# psu.net
KiCad netlist of a schematic drawn in Altium Designer
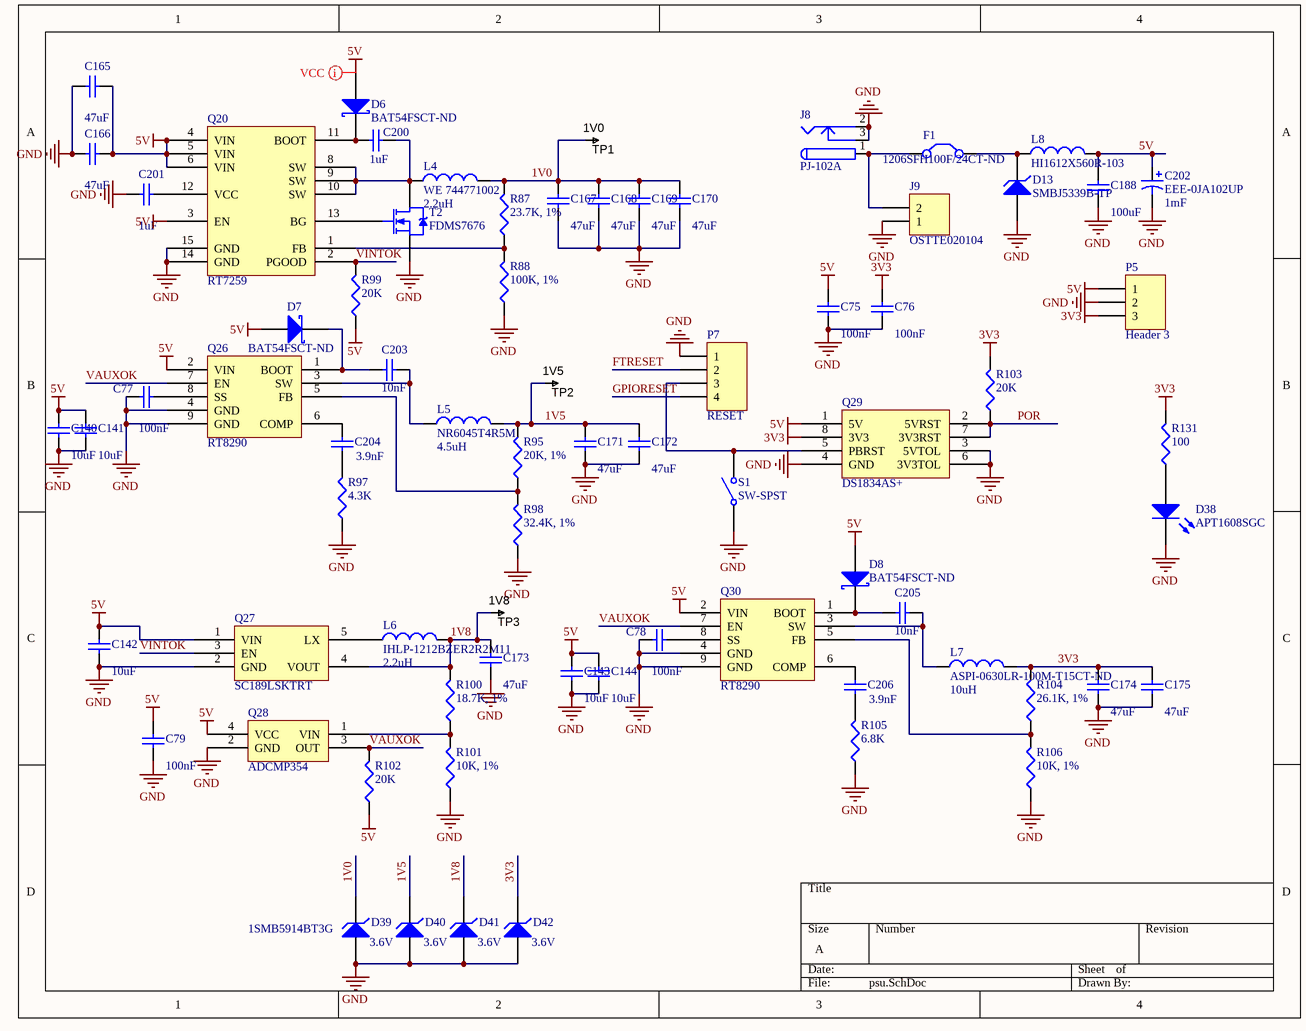
[diagram p0: psu.SchDoc]

(export (version "E")
  (design (tool "Eeschema 10.0.6"))
  (components
    (comp (ref "C75")
      (value "100nF")
      (footprint "CAPC1005X06L")
      (description "Capacitor")
      (fields (field (name "Comment") "Cap") (field (name "PUBLISHER") "Altium Limited"))
      (libsource (lib "Miscellaneous Devices") (part "Cap"))
    )
    (comp (ref "C76")
      (value "100nF")
      (footprint "CAPC1005X06L")
      (description "Capacitor")
      (fields (field (name "Comment") "Cap") (field (name "PUBLISHER") "Altium Limited"))
      (libsource (lib "Miscellaneous Devices") (part "Cap"))
    )
    (comp (ref "C77")
      (value "100nF")
      (footprint "CAPC1005X06L")
      (description "Capacitor")
      (fields (field (name "Comment") "Cap") (field (name "PUBLISHER") "Altium Limited"))
      (libsource (lib "Miscellaneous Devices") (part "Cap"))
    )
    (comp (ref "C78")
      (value "100nF")
      (footprint "CAPC1005X06L")
      (description "Capacitor")
      (fields (field (name "Comment") "Cap") (field (name "PUBLISHER") "Altium Limited"))
      (libsource (lib "Miscellaneous Devices") (part "Cap"))
    )
    (comp (ref "C79")
      (value "100nF")
      (footprint "CAPC1005X06L")
      (description "Capacitor")
      (fields (field (name "Comment") "Cap") (field (name "PUBLISHER") "Altium Limited"))
      (libsource (lib "Miscellaneous Devices") (part "Cap"))
    )
    (comp (ref "C140")
      (value "10uF")
      (footprint "CAPC1608X90N")
      (description "Capacitor")
      (fields (field (name "Comment") "GRM188R60G106ME47") (field (name "PUBLISHER") "Altium Limited"))
      (libsource (lib "Miscellaneous Devices") (part "Cap"))
    )
    (comp (ref "C141")
      (value "10uF")
      (footprint "CAPC1608X90N")
      (description "Capacitor")
      (fields (field (name "Comment") "GRM188R60G106ME47") (field (name "PUBLISHER") "Altium Limited"))
      (libsource (lib "Miscellaneous Devices") (part "Cap"))
    )
    (comp (ref "C142")
      (value "10uF")
      (footprint "CAPC1608X90N")
      (description "Capacitor")
      (fields (field (name "Comment") "GRM188R60G106ME47") (field (name "PUBLISHER") "Altium Limited"))
      (libsource (lib "Miscellaneous Devices") (part "Cap"))
    )
    (comp (ref "C143")
      (value "10uF")
      (footprint "CAPC1608X90N")
      (description "Capacitor")
      (fields (field (name "Comment") "GRM188R60G106ME47") (field (name "PUBLISHER") "Altium Limited"))
      (libsource (lib "Miscellaneous Devices") (part "Cap"))
    )
    (comp (ref "C144")
      (value "10uF")
      (footprint "CAPC1608X90N")
      (description "Capacitor")
      (fields (field (name "Comment") "GRM188R60G106ME47") (field (name "PUBLISHER") "Altium Limited"))
      (libsource (lib "Miscellaneous Devices") (part "Cap"))
    )
    (comp (ref "C165")
      (value "47uF")
      (footprint "CAPC3225X220N")
      (description "Capacitor")
      (fields (field (name "Comment") "GRM31CR60J476ME19L") (field (name "PUBLISHER") "Altium Limited"))
      (libsource (lib "Miscellaneous Devices") (part "Cap"))
    )
    (comp (ref "C166")
      (value "47uF")
      (footprint "CAPC3225X220N")
      (description "Capacitor")
      (fields (field (name "Comment") "GRM31CR60J476ME19L") (field (name "PUBLISHER") "Altium Limited"))
      (libsource (lib "Miscellaneous Devices") (part "Cap"))
    )
    (comp (ref "C167")
      (value "47uF")
      (footprint "CAPC3225X220N")
      (description "Capacitor")
      (fields (field (name "Comment") "GRM31CR60J476ME19L") (field (name "PUBLISHER") "Altium Limited"))
      (libsource (lib "Miscellaneous Devices") (part "Cap"))
    )
    (comp (ref "C168")
      (value "47uF")
      (footprint "CAPC3225X220N")
      (description "Capacitor")
      (fields (field (name "Comment") "GRM31CR60J476ME19L") (field (name "PUBLISHER") "Altium Limited"))
      (libsource (lib "Miscellaneous Devices") (part "Cap"))
    )
    (comp (ref "C169")
      (value "47uF")
      (footprint "CAPC3225X220N")
      (description "Capacitor")
      (fields (field (name "Comment") "GRM31CR60J476ME19L") (field (name "PUBLISHER") "Altium Limited"))
      (libsource (lib "Miscellaneous Devices") (part "Cap"))
    )
    (comp (ref "C170")
      (value "47uF")
      (footprint "CAPC3225X220N")
      (description "Capacitor")
      (fields (field (name "Comment") "GRM31CR60J476ME19L") (field (name "PUBLISHER") "Altium Limited"))
      (libsource (lib "Miscellaneous Devices") (part "Cap"))
    )
    (comp (ref "C171")
      (value "47uF")
      (footprint "CAPC3225X220N")
      (description "Capacitor")
      (fields (field (name "Comment") "GRM31CR60J476ME19L") (field (name "PUBLISHER") "Altium Limited"))
      (libsource (lib "Miscellaneous Devices") (part "Cap"))
    )
    (comp (ref "C172")
      (value "47uF")
      (footprint "CAPC3225X220N")
      (description "Capacitor")
      (fields (field (name "Comment") "GRM31CR60J476ME19L") (field (name "PUBLISHER") "Altium Limited"))
      (libsource (lib "Miscellaneous Devices") (part "Cap"))
    )
    (comp (ref "C173")
      (value "47uF")
      (footprint "CAPC3225X220N")
      (description "Capacitor")
      (fields (field (name "Comment") "GRM31CR60J476ME19L") (field (name "PUBLISHER") "Altium Limited"))
      (libsource (lib "Miscellaneous Devices") (part "Cap"))
    )
    (comp (ref "C174")
      (value "47uF")
      (footprint "CAPC3225X220N")
      (description "Capacitor")
      (fields (field (name "Comment") "GRM31CR60J476ME19L") (field (name "PUBLISHER") "Altium Limited"))
      (libsource (lib "Miscellaneous Devices") (part "Cap"))
    )
    (comp (ref "C175")
      (value "47uF")
      (footprint "CAPC3225X220N")
      (description "Capacitor")
      (fields (field (name "Comment") "GRM31CR60J476ME19L") (field (name "PUBLISHER") "Altium Limited"))
      (libsource (lib "Miscellaneous Devices") (part "Cap"))
    )
    (comp (ref "C188")
      (value "100uF")
      (footprint "CAPC3225X220N")
      (description "Capacitor")
      (fields (field (name "Comment") "GRM31CR60J107ME39L") (field (name "PUBLISHER") "Altium Limited"))
      (libsource (lib "Miscellaneous Devices") (part "Cap"))
    )
    (comp (ref "C200")
      (value "1uF")
      (footprint "CAPC1608X90N")
      (description "Capacitor")
      (fields (field (name "Comment") "GRM188R60J105KA01D") (field (name "PUBLISHER") "Altium Limited"))
      (libsource (lib "Miscellaneous Devices") (part "Cap"))
    )
    (comp (ref "C201")
      (value "1uF")
      (footprint "CAPC1608X90N")
      (description "Capacitor")
      (fields (field (name "Comment") "GRM188R60J105KA01D") (field (name "PUBLISHER") "Altium Limited"))
      (libsource (lib "Miscellaneous Devices") (part "Cap"))
    )
    (comp (ref "C202")
      (value "EEE-0JA102UP")
      (footprint "CAP_ELEC_SIZE_E")
      (description "Polarized Capacitor (Radial)")
      (fields (field (name "ALTIUM_VALUE") "1mF") (field (name "PUBLISHER") "Altium Limited"))
      (libsource (lib "Miscellaneous Devices") (part "Cap Pol1"))
    )
    (comp (ref "C203")
      (value "10nF")
      (footprint "CAPC1005X06L")
      (description "Capacitor")
      (fields (field (name "Comment") "GRM188R71H103KA01D") (field (name "PUBLISHER") "Altium Limited"))
      (libsource (lib "Miscellaneous Devices") (part "Cap"))
    )
    (comp (ref "C204")
      (value "3.9nF")
      (footprint "CAPC1608X90N")
      (description "Capacitor")
      (fields (field (name "Comment") "CL10B393KO8NNNC") (field (name "PUBLISHER") "Altium Limited"))
      (libsource (lib "Miscellaneous Devices") (part "Cap"))
    )
    (comp (ref "C205")
      (value "10nF")
      (footprint "CAPC1005X06L")
      (description "Capacitor")
      (fields (field (name "Comment") "GRM188R71H103KA01D") (field (name "PUBLISHER") "Altium Limited"))
      (libsource (lib "Miscellaneous Devices") (part "Cap"))
    )
    (comp (ref "C206")
      (value "3.9nF")
      (footprint "CAPC1608X90N")
      (description "Capacitor")
      (fields (field (name "Comment") "CL10B393KO8NNNC") (field (name "PUBLISHER") "Altium Limited"))
      (libsource (lib "Miscellaneous Devices") (part "Cap"))
    )
    (comp (ref "D6")
      (value "BAT54FSCT-ND")
      (footprint "BAT54")
      (description "Schottky Diode")
      (fields (field (name "PUBLISHER") "Altium Limited"))
      (libsource (lib "Miscellaneous Devices") (part "D Schottky"))
    )
    (comp (ref "D7")
      (value "BAT54FSCT-ND")
      (footprint "BAT54")
      (description "Schottky Diode")
      (fields (field (name "PUBLISHER") "Altium Limited"))
      (libsource (lib "Miscellaneous Devices") (part "D Schottky"))
    )
    (comp (ref "D8")
      (value "BAT54FSCT-ND")
      (footprint "BAT54")
      (description "Schottky Diode")
      (fields (field (name "PUBLISHER") "Altium Limited"))
      (libsource (lib "Miscellaneous Devices") (part "D Schottky"))
    )
    (comp (ref "D13")
      (value "SMBJ5339B-TP")
      (footprint "DO-214AA")
      (description "Zener Diode")
      (fields (field (name "PUBLISHER") "Altium Limited"))
      (libsource (lib "Miscellaneous Devices") (part "D Zener"))
    )
    (comp (ref "D38")
      (value "APT1608SGC")
      (footprint "LED-0603")
      (description "Typical RED, GREEN, YELLOW, AMBER GaAs LED")
      (fields (field (name "PUBLISHER") "Altium Limited"))
      (libsource (lib "Miscellaneous Devices") (part "LED2"))
    )
    (comp (ref "D39")
      (value "1SMB5914BT3G")
      (footprint "DO-214AA")
      (description "Zener Diode")
      (fields (field (name "ALTIUM_VALUE") "3.6V") (field (name "PUBLISHER") "Altium Limited"))
      (libsource (lib "Miscellaneous Devices") (part "D Zener"))
    )
    (comp (ref "D40")
      (value "3.6V")
      (footprint "DO-214AA")
      (description "Zener Diode")
      (fields (field (name "Comment") "1SMB5914BT3G") (field (name "PUBLISHER") "Altium Limited"))
      (libsource (lib "Miscellaneous Devices") (part "D Zener"))
    )
    (comp (ref "D41")
      (value "3.6V")
      (footprint "DO-214AA")
      (description "Zener Diode")
      (fields (field (name "Comment") "1SMB5914BT3G") (field (name "PUBLISHER") "Altium Limited"))
      (libsource (lib "Miscellaneous Devices") (part "D Zener"))
    )
    (comp (ref "D42")
      (value "3.6V")
      (footprint "DO-214AA")
      (description "Zener Diode")
      (fields (field (name "Comment") "1SMB5914BT3G") (field (name "PUBLISHER") "Altium Limited"))
      (libsource (lib "Miscellaneous Devices") (part "D Zener"))
    )
    (comp (ref "F1")
      (value "1206SFH100F/24CT-ND")
      (footprint "CAPC3225X220N")
      (description "10A Fuse")
      (fields (field (name "PUBLISHER") "Altium Limited"))
      (libsource (lib "Miscellaneous Devices") (part "Jumper"))
    )
    (comp (ref "J8")
      (value "PJ-102A")
      (footprint "PJ-102A")
      (description "Low Voltage Power Supply Connector")
      (fields (field (name "PUBLISHER") "Altium Limited"))
      (libsource (lib "Miscellaneous Connectors") (part "PWR2.5"))
    )
    (comp (ref "J9")
      (value "OSTTE020104")
      (footprint "OSTTEE02014")
      (description "Header, 2-Pin")
      (fields (field (name "PUBLISHER") "Altium Limited"))
      (libsource (lib "Miscellaneous Connectors") (part "Header 2"))
    )
    (comp (ref "L4")
      (value "WE 744771002")
      (footprint "WE 744771002")
      (description "Inductor")
      (fields (field (name "ALTIUM_VALUE") "2.2uH") (field (name "PUBLISHER") "Altium Limited"))
      (libsource (lib "Miscellaneous Devices") (part "Inductor"))
    )
    (comp (ref "L5")
      (value "NR6045T4R5M")
      (footprint "NR6045")
      (description "Inductor")
      (fields (field (name "ALTIUM_VALUE") "4.5uH") (field (name "PUBLISHER") "Altium Limited"))
      (libsource (lib "Miscellaneous Devices") (part "Inductor"))
    )
    (comp (ref "L6")
      (value "IHLP-1212BZER2R2M11")
      (footprint "IHLP-1212BZ")
      (description "Inductor")
      (fields (field (name "ALTIUM_VALUE") "2.2uH") (field (name "PUBLISHER") "Altium Limited"))
      (libsource (lib "Miscellaneous Devices") (part "Inductor"))
    )
    (comp (ref "L7")
      (value "ASPI-0630LR-100M-T15CT-ND")
      (footprint "ASPI-0630LR")
      (description "Inductor")
      (fields (field (name "ALTIUM_VALUE") "10uH") (field (name "PUBLISHER") "Altium Limited"))
      (libsource (lib "Miscellaneous Devices") (part "Inductor"))
    )
    (comp (ref "L8")
      (value "HI1612X560R-103")
      (footprint "IND1612")
      (description "Inductor")
      (fields (field (name "PUBLISHER") "Altium Limited"))
      (libsource (lib "Miscellaneous Devices") (part "Inductor"))
    )
    (comp (ref "P5")
      (value "Header 3")
      (footprint "HDR1X3")
      (description "Header, 3-Pin")
      (fields (field (name "PUBLISHER") "Altium Limited"))
      (libsource (lib "Miscellaneous Connectors") (part "Header 3"))
    )
    (comp (ref "P7")
      (value "RESET")
      (footprint "HDR1X4")
      (description "Header, 4-Pin")
      (fields (field (name "PUBLISHER") "Altium Limited"))
      (libsource (lib "Miscellaneous Connectors") (part "Header 4"))
    )
    (comp (ref "Q20") (value "RT7259") (footprint "WFDN-14L 4x3") (libsource (lib "schlib") (part "RT7259")))
    (comp (ref "Q26")
      (value "RT8290")
      (footprint "SOIC127P600X135_HS-9N")
      (libsource (lib "schlib") (part "RT8290"))
    )
    (comp (ref "Q27") (value "SC189LSKTRT") (footprint "SOT23-5") (libsource (lib "schlib") (part "SC189")))
    (comp (ref "Q28") (value "ADCMP354") (footprint "SC70-4") (libsource (lib "schlib") (part "ADCMP354")))
    (comp (ref "Q29")
      (value "DS1834AS+")
      (footprint "SOIC127P600X175-8AN")
      (libsource (lib "schlib") (part "DS1834"))
    )
    (comp (ref "Q30")
      (value "RT8290")
      (footprint "SOIC127P600X135_HS-9N")
      (libsource (lib "schlib") (part "RT8290"))
    )
    (comp (ref "R87")
      (value "23.7K, 1%")
      (footprint "J1-0603")
      (description "Resistor")
      (fields (field (name "Comment") "RC1608F2372CS") (field (name "PUBLISHER") "Altium Limited"))
      (libsource (lib "Miscellaneous Devices") (part "Res3"))
    )
    (comp (ref "R88")
      (value "100K, 1%")
      (footprint "J1-0603")
      (description "Resistor")
      (fields (field (name "Comment") "RC1608F104CS") (field (name "PUBLISHER") "Altium Limited"))
      (libsource (lib "Miscellaneous Devices") (part "Res3"))
    )
    (comp (ref "R95")
      (value "20K, 1%")
      (footprint "J1-0603")
      (description "Resistor")
      (fields (field (name "Comment") "RC1608F203CS") (field (name "PUBLISHER") "Altium Limited"))
      (libsource (lib "Miscellaneous Devices") (part "Res3"))
    )
    (comp (ref "R97")
      (value "4.3K")
      (footprint "J1-0603")
      (description "Resistor")
      (fields (field (name "Comment") "RC1608F432CS") (field (name "PUBLISHER") "Altium Limited"))
      (libsource (lib "Miscellaneous Devices") (part "Res3"))
    )
    (comp (ref "R98")
      (value "32.4K, 1%")
      (footprint "J1-0603")
      (description "Resistor")
      (fields (field (name "Comment") "RC1608F3242CS") (field (name "PUBLISHER") "Altium Limited"))
      (libsource (lib "Miscellaneous Devices") (part "Res3"))
    )
    (comp (ref "R99")
      (value "20K")
      (footprint "J1-0603")
      (description "Resistor")
      (fields (field (name "Comment") "RC1608F203CS") (field (name "PUBLISHER") "Altium Limited"))
      (libsource (lib "Miscellaneous Devices") (part "Res3"))
    )
    (comp (ref "R100")
      (value "18.7K, 1%")
      (footprint "J1-0603")
      (description "Resistor")
      (fields (field (name "Comment") "RC1608F1872CS") (field (name "PUBLISHER") "Altium Limited"))
      (libsource (lib "Miscellaneous Devices") (part "Res3"))
    )
    (comp (ref "R101")
      (value "10K, 1%")
      (footprint "J1-0603")
      (description "Resistor")
      (fields (field (name "Comment") "RC1608F103CS") (field (name "PUBLISHER") "Altium Limited"))
      (libsource (lib "Miscellaneous Devices") (part "Res3"))
    )
    (comp (ref "R102")
      (value "20K")
      (footprint "J1-0603")
      (description "Resistor")
      (fields (field (name "Comment") "RC1608F203CS") (field (name "PUBLISHER") "Altium Limited"))
      (libsource (lib "Miscellaneous Devices") (part "Res3"))
    )
    (comp (ref "R103")
      (value "20K")
      (footprint "J1-0603")
      (description "Resistor")
      (fields (field (name "Comment") "RC1608F203CS") (field (name "PUBLISHER") "Altium Limited"))
      (libsource (lib "Miscellaneous Devices") (part "Res3"))
    )
    (comp (ref "R104")
      (value "26.1K, 1%")
      (footprint "J1-0603")
      (description "Resistor")
      (fields (field (name "Comment") "RC1608F2612CS") (field (name "PUBLISHER") "Altium Limited"))
      (libsource (lib "Miscellaneous Devices") (part "Res3"))
    )
    (comp (ref "R105")
      (value "6.8K")
      (footprint "J1-0603")
      (description "Resistor")
      (fields (field (name "Comment") "RC1608F682CS") (field (name "PUBLISHER") "Altium Limited"))
      (libsource (lib "Miscellaneous Devices") (part "Res3"))
    )
    (comp (ref "R106")
      (value "10K, 1%")
      (footprint "J1-0603")
      (description "Resistor")
      (fields (field (name "Comment") "RC1608F103CS") (field (name "PUBLISHER") "Altium Limited"))
      (libsource (lib "Miscellaneous Devices") (part "Res3"))
    )
    (comp (ref "R131")
      (value "100")
      (footprint "J1-0603")
      (description "Resistor")
      (fields (field (name "Comment") "RC1608F101CS"))
      (libsource (lib "Miscellaneous Devices") (part "Res3"))
    )
    (comp (ref "S1")
      (value "SW-SPST")
      (footprint "FSM4JSMA")
      (description "Single-Pole, Single-Throw Switch")
      (fields (field (name "PUBLISHER") "Altium Limited"))
      (libsource (lib "Miscellaneous Devices") (part "SW-SPST"))
    )
    (comp (ref "T2")
      (value "FDMS7676")
      (footprint "PowerSO8")
      (description "N-Channel Power MOSFET")
      (fields (field (name "PUBLISHER") "Altium Limited"))
      (libsource (lib "Miscellaneous Devices") (part "NMOS-2"))
    )
    (comp (ref "TP1")
      (value "1V0")
      (footprint "TP-R60")
      (description "SMD test pin")
      (libsource (lib "PBL - Test Points") (part "TESTPOINT"))
    )
    (comp (ref "TP2")
      (value "1V5")
      (footprint "TP-R60")
      (description "SMD test pin")
      (libsource (lib "PBL - Test Points") (part "TESTPOINT"))
    )
    (comp (ref "TP3")
      (value "1V8")
      (footprint "TP-R60")
      (description "SMD test pin")
      (libsource (lib "PBL - Test Points") (part "TESTPOINT"))
    )
  )
  (nets
    (net (code "1") (name "/1V0") (class "Default")
      (node (ref "C167") (pin "2") (pinfunction "2_2") (pintype "passive"))
      (node (ref "C168") (pin "2") (pinfunction "2_2") (pintype "passive"))
      (node (ref "C169") (pin "2") (pinfunction "2_2") (pintype "passive"))
      (node (ref "C170") (pin "2") (pinfunction "2_2") (pintype "passive"))
      (node (ref "D39") (pin "K") (pinfunction "K_K") (pintype "passive"))
      (node (ref "L4") (pin "2") (pinfunction "2_2") (pintype "passive"))
      (node (ref "R87") (pin "2") (pinfunction "2_2") (pintype "passive"))
      (node (ref "TP1") (pin "1") (pintype "passive"))
    )
    (net (code "2") (name "/1V5") (class "Default")
      (node (ref "C171") (pin "2") (pinfunction "2_2") (pintype "passive"))
      (node (ref "C172") (pin "2") (pinfunction "2_2") (pintype "passive"))
      (node (ref "D40") (pin "K") (pinfunction "K_K") (pintype "passive"))
      (node (ref "L5") (pin "2") (pinfunction "2_2") (pintype "passive"))
      (node (ref "R95") (pin "2") (pinfunction "2_2") (pintype "passive"))
      (node (ref "TP2") (pin "1") (pintype "passive"))
    )
    (net (code "3") (name "/1V8") (class "Default")
      (node (ref "C173") (pin "2") (pinfunction "2_2") (pintype "passive"))
      (node (ref "D41") (pin "K") (pinfunction "K_K") (pintype "passive"))
      (node (ref "L6") (pin "2") (pinfunction "2_2") (pintype "passive"))
      (node (ref "Q27") (pin "4") (pinfunction "VOUT_4") (pintype "passive"))
      (node (ref "R100") (pin "2") (pinfunction "2_2") (pintype "passive"))
      (node (ref "TP3") (pin "1") (pintype "passive"))
    )
    (net (code "4") (name "/FTRESET") (class "Default")
      (node (ref "P7") (pin "2") (pinfunction "2_2") (pintype "passive"))
    )
    (net (code "5") (name "/GPIORESET") (class "Default")
      (node (ref "P7") (pin "4") (pinfunction "4_4") (pintype "passive"))
    )
    (net (code "6") (name "/POR") (class "Default")
      (node (ref "Q29") (pin "2") (pinfunction "5VRST_2") (pintype "passive"))
      (node (ref "Q29") (pin "7") (pinfunction "3V3RST_7") (pintype "passive"))
      (node (ref "R103") (pin "1") (pinfunction "1_1") (pintype "passive"))
    )
    (net (code "7") (name "/VAUXOK") (class "Default")
      (node (ref "Q26") (pin "7") (pinfunction "EN_7") (pintype "passive"))
      (node (ref "Q28") (pin "3") (pinfunction "OUT_3") (pintype "passive"))
      (node (ref "Q30") (pin "7") (pinfunction "EN_7") (pintype "passive"))
      (node (ref "R102") (pin "2") (pinfunction "2_2") (pintype "passive"))
    )
    (net (code "8") (name "/VINTOK") (class "Default")
      (node (ref "Q20") (pin "2") (pinfunction "PGOOD_2") (pintype "passive"))
      (node (ref "Q27") (pin "3") (pinfunction "EN_3") (pintype "passive"))
      (node (ref "R99") (pin "2") (pinfunction "2_2") (pintype "passive"))
    )
    (net (code "9") (name "3V3") (class "Default")
      (node (ref "C174") (pin "2") (pinfunction "2_2") (pintype "passive"))
      (node (ref "C175") (pin "2") (pinfunction "2_2") (pintype "passive"))
      (node (ref "C76") (pin "2") (pinfunction "2_2") (pintype "passive"))
      (node (ref "D42") (pin "K") (pinfunction "K_K") (pintype "passive"))
      (node (ref "L7") (pin "2") (pinfunction "2_2") (pintype "passive"))
      (node (ref "P5") (pin "3") (pinfunction "3_3") (pintype "passive"))
      (node (ref "Q29") (pin "8") (pinfunction "3V3_8") (pintype "passive"))
      (node (ref "R103") (pin "2") (pinfunction "2_2") (pintype "passive"))
      (node (ref "R104") (pin "2") (pinfunction "2_2") (pintype "passive"))
      (node (ref "R131") (pin "2") (pinfunction "2_2") (pintype "passive"))
    )
    (net (code "10") (name "5V") (class "Default")
      (node (ref "C140") (pin "2") (pinfunction "2_2") (pintype "passive"))
      (node (ref "C141") (pin "2") (pinfunction "2_2") (pintype "passive"))
      (node (ref "C142") (pin "2") (pinfunction "2_2") (pintype "passive"))
      (node (ref "C143") (pin "2") (pinfunction "2_2") (pintype "passive"))
      (node (ref "C144") (pin "2") (pinfunction "2_2") (pintype "passive"))
      (node (ref "C165") (pin "2") (pinfunction "2_2") (pintype "passive"))
      (node (ref "C166") (pin "2") (pinfunction "2_2") (pintype "passive"))
      (node (ref "C188") (pin "2") (pinfunction "2_2") (pintype "passive"))
      (node (ref "C202") (pin "1") (pinfunction "1_1") (pintype "passive"))
      (node (ref "C75") (pin "2") (pinfunction "2_2") (pintype "passive"))
      (node (ref "C79") (pin "2") (pinfunction "2_2") (pintype "passive"))
      (node (ref "D6") (pin "1") (pinfunction "A_1") (pintype "passive"))
      (node (ref "D7") (pin "1") (pinfunction "A_1") (pintype "passive"))
      (node (ref "D8") (pin "1") (pinfunction "A_1") (pintype "passive"))
      (node (ref "L8") (pin "2") (pinfunction "2_2") (pintype "passive"))
      (node (ref "P5") (pin "1") (pinfunction "1_1") (pintype "passive"))
      (node (ref "Q20") (pin "3") (pinfunction "EN_3") (pintype "passive"))
      (node (ref "Q20") (pin "4") (pinfunction "VIN_4") (pintype "passive"))
      (node (ref "Q20") (pin "5") (pinfunction "VIN_5") (pintype "passive"))
      (node (ref "Q20") (pin "6") (pinfunction "VIN_6") (pintype "passive"))
      (node (ref "Q26") (pin "2") (pinfunction "VIN_2") (pintype "passive"))
      (node (ref "Q27") (pin "1") (pinfunction "VIN_1") (pintype "passive"))
      (node (ref "Q28") (pin "4") (pinfunction "VCC_4") (pintype "passive"))
      (node (ref "Q29") (pin "1") (pinfunction "5V_1") (pintype "passive"))
      (node (ref "Q30") (pin "2") (pinfunction "VIN_2") (pintype "passive"))
      (node (ref "R102") (pin "1") (pinfunction "1_1") (pintype "passive"))
      (node (ref "R99") (pin "1") (pinfunction "1_1") (pintype "passive"))
    )
    (net (code "11") (name "GND") (class "Default")
      (node (ref "C140") (pin "1") (pinfunction "1_1") (pintype "passive"))
      (node (ref "C141") (pin "1") (pinfunction "1_1") (pintype "passive"))
      (node (ref "C142") (pin "1") (pinfunction "1_1") (pintype "passive"))
      (node (ref "C143") (pin "1") (pinfunction "1_1") (pintype "passive"))
      (node (ref "C144") (pin "1") (pinfunction "1_1") (pintype "passive"))
      (node (ref "C165") (pin "1") (pinfunction "1_1") (pintype "passive"))
      (node (ref "C166") (pin "1") (pinfunction "1_1") (pintype "passive"))
      (node (ref "C167") (pin "1") (pinfunction "1_1") (pintype "passive"))
      (node (ref "C168") (pin "1") (pinfunction "1_1") (pintype "passive"))
      (node (ref "C169") (pin "1") (pinfunction "1_1") (pintype "passive"))
      (node (ref "C170") (pin "1") (pinfunction "1_1") (pintype "passive"))
      (node (ref "C171") (pin "1") (pinfunction "1_1") (pintype "passive"))
      (node (ref "C172") (pin "1") (pinfunction "1_1") (pintype "passive"))
      (node (ref "C173") (pin "1") (pinfunction "1_1") (pintype "passive"))
      (node (ref "C174") (pin "1") (pinfunction "1_1") (pintype "passive"))
      (node (ref "C175") (pin "1") (pinfunction "1_1") (pintype "passive"))
      (node (ref "C188") (pin "1") (pinfunction "1_1") (pintype "passive"))
      (node (ref "C201") (pin "2") (pinfunction "2_2") (pintype "passive"))
      (node (ref "C202") (pin "2") (pinfunction "2_2") (pintype "passive"))
      (node (ref "C75") (pin "1") (pinfunction "1_1") (pintype "passive"))
      (node (ref "C76") (pin "1") (pinfunction "1_1") (pintype "passive"))
      (node (ref "C77") (pin "1") (pinfunction "1_1") (pintype "passive"))
      (node (ref "C78") (pin "1") (pinfunction "1_1") (pintype "passive"))
      (node (ref "C79") (pin "1") (pinfunction "1_1") (pintype "passive"))
      (node (ref "D13") (pin "A") (pinfunction "A_A") (pintype "passive"))
      (node (ref "D38") (pin "K") (pinfunction "K_K") (pintype "passive"))
      (node (ref "D39") (pin "A") (pinfunction "A_A") (pintype "passive"))
      (node (ref "D40") (pin "A") (pinfunction "A_A") (pintype "passive"))
      (node (ref "D41") (pin "A") (pinfunction "A_A") (pintype "passive"))
      (node (ref "D42") (pin "A") (pinfunction "A_A") (pintype "passive"))
      (node (ref "J8") (pin "2") (pinfunction "2_2") (pintype "power_in"))
      (node (ref "J8") (pin "3") (pinfunction "3_3") (pintype "power_in"))
      (node (ref "J9") (pin "1") (pinfunction "1_1") (pintype "passive"))
      (node (ref "P5") (pin "2") (pinfunction "2_2") (pintype "passive"))
      (node (ref "P7") (pin "1") (pinfunction "1_1") (pintype "passive"))
      (node (ref "Q20") (pin "14") (pinfunction "GND_14") (pintype "passive"))
      (node (ref "Q20") (pin "15") (pinfunction "GND_15") (pintype "passive"))
      (node (ref "Q26") (pin "4") (pinfunction "GND_4") (pintype "passive"))
      (node (ref "Q26") (pin "9") (pinfunction "GND_9") (pintype "passive"))
      (node (ref "Q27") (pin "2") (pinfunction "GND_2") (pintype "passive"))
      (node (ref "Q28") (pin "2") (pinfunction "GND_2") (pintype "passive"))
      (node (ref "Q29") (pin "3") (pinfunction "5VTOL_3") (pintype "passive"))
      (node (ref "Q29") (pin "4") (pinfunction "GND_4") (pintype "passive"))
      (node (ref "Q29") (pin "6") (pinfunction "3V3TOL_6") (pintype "passive"))
      (node (ref "Q30") (pin "4") (pinfunction "GND_4") (pintype "passive"))
      (node (ref "Q30") (pin "9") (pinfunction "GND_9") (pintype "passive"))
      (node (ref "R101") (pin "1") (pinfunction "1_1") (pintype "passive"))
      (node (ref "R105") (pin "1") (pinfunction "1_1") (pintype "passive"))
      (node (ref "R106") (pin "1") (pinfunction "1_1") (pintype "passive"))
      (node (ref "R88") (pin "1") (pinfunction "1_1") (pintype "passive"))
      (node (ref "R97") (pin "1") (pinfunction "1_1") (pintype "passive"))
      (node (ref "R98") (pin "1") (pinfunction "1_1") (pintype "passive"))
      (node (ref "S1") (pin "4") (pinfunction "COMMON_4") (pintype "passive"))
      (node (ref "T2") (pin "3") (pinfunction "S_3") (pintype "passive"))
    )
    (net (code "12") (name "Net-(C204-Pad1)") (class "Default")
      (node (ref "C204") (pin "1") (pinfunction "1_1") (pintype "passive"))
      (node (ref "R97") (pin "2") (pinfunction "2_2") (pintype "passive"))
    )
    (net (code "13") (name "Net-(C206-Pad1)") (class "Default")
      (node (ref "C206") (pin "1") (pinfunction "1_1") (pintype "passive"))
      (node (ref "R105") (pin "2") (pinfunction "2_2") (pintype "passive"))
    )
    (net (code "14") (name "Net-(D6-K)") (class "Default")
      (node (ref "C200") (pin "2") (pinfunction "2_2") (pintype "passive"))
      (node (ref "D6") (pin "2") (pinfunction "K_2") (pintype "passive"))
      (node (ref "Q20") (pin "11") (pinfunction "BOOT_11") (pintype "passive"))
    )
    (net (code "15") (name "Net-(D7-K)") (class "Default")
      (node (ref "C203") (pin "2") (pinfunction "2_2") (pintype "passive"))
      (node (ref "D7") (pin "2") (pinfunction "K_2") (pintype "passive"))
      (node (ref "Q26") (pin "1") (pinfunction "BOOT_1") (pintype "passive"))
    )
    (net (code "16") (name "Net-(D8-K)") (class "Default")
      (node (ref "C205") (pin "2") (pinfunction "2_2") (pintype "passive"))
      (node (ref "D8") (pin "2") (pinfunction "K_2") (pintype "passive"))
      (node (ref "Q30") (pin "1") (pinfunction "BOOT_1") (pintype "passive"))
    )
    (net (code "17") (name "Net-(D38-PadA)") (class "Default")
      (node (ref "D38") (pin "A") (pinfunction "A_A") (pintype "passive"))
      (node (ref "R131") (pin "1") (pinfunction "1_1") (pintype "passive"))
    )
    (net (code "18") (name "Net-(F1-C1)") (class "Default")
      (node (ref "F1") (pin "1") (pinfunction "C1_1") (pintype "passive"))
      (node (ref "J8") (pin "1") (pinfunction "1_1") (pintype "power_in"))
      (node (ref "J9") (pin "2") (pinfunction "2_2") (pintype "passive"))
    )
    (net (code "19") (name "Net-(F1-C2)") (class "Default")
      (node (ref "D13") (pin "K") (pinfunction "K_K") (pintype "passive"))
      (node (ref "F1") (pin "2") (pinfunction "C2_2") (pintype "passive"))
      (node (ref "L8") (pin "1") (pinfunction "1_1") (pintype "passive"))
    )
    (net (code "20") (name "Net-(Q20-BG)") (class "Default")
      (node (ref "Q20") (pin "13") (pinfunction "BG_13") (pintype "passive"))
      (node (ref "T2") (pin "1") (pinfunction "G_1") (pintype "passive"))
    )
    (net (code "21") (name "Net-(Q20-FB)") (class "Default")
      (node (ref "Q20") (pin "1") (pinfunction "FB_1") (pintype "passive"))
      (node (ref "R87") (pin "1") (pinfunction "1_1") (pintype "passive"))
      (node (ref "R88") (pin "2") (pinfunction "2_2") (pintype "passive"))
    )
    (net (code "22") (name "Net-(Q20-VCC)") (class "Default")
      (node (ref "C201") (pin "1") (pinfunction "1_1") (pintype "passive"))
      (node (ref "Q20") (pin "12") (pinfunction "VCC_12") (pintype "passive"))
    )
    (net (code "23") (name "Net-(Q26-COMP)") (class "Default")
      (node (ref "C204") (pin "2") (pinfunction "2_2") (pintype "passive"))
      (node (ref "Q26") (pin "6") (pinfunction "COMP_6") (pintype "passive"))
    )
    (net (code "24") (name "Net-(Q26-FB)") (class "Default")
      (node (ref "Q26") (pin "5") (pinfunction "FB_5") (pintype "passive"))
      (node (ref "R95") (pin "1") (pinfunction "1_1") (pintype "passive"))
      (node (ref "R98") (pin "2") (pinfunction "2_2") (pintype "passive"))
    )
    (net (code "25") (name "Net-(Q26-SS)") (class "Default")
      (node (ref "C77") (pin "2") (pinfunction "2_2") (pintype "passive"))
      (node (ref "Q26") (pin "8") (pinfunction "SS_8") (pintype "passive"))
    )
    (net (code "26") (name "Net-(Q26-SW)") (class "Default")
      (node (ref "C203") (pin "1") (pinfunction "1_1") (pintype "passive"))
      (node (ref "L5") (pin "1") (pinfunction "1_1") (pintype "passive"))
      (node (ref "Q26") (pin "3") (pinfunction "SW_3") (pintype "passive"))
    )
    (net (code "27") (name "Net-(Q27-LX)") (class "Default")
      (node (ref "L6") (pin "1") (pinfunction "1_1") (pintype "passive"))
      (node (ref "Q27") (pin "5") (pinfunction "LX_5") (pintype "passive"))
    )
    (net (code "28") (name "Net-(Q28-VIN)") (class "Default")
      (node (ref "Q28") (pin "1") (pinfunction "VIN_1") (pintype "passive"))
      (node (ref "R100") (pin "1") (pinfunction "1_1") (pintype "passive"))
      (node (ref "R101") (pin "2") (pinfunction "2_2") (pintype "passive"))
    )
    (net (code "29") (name "Net-(Q29-PBRST)") (class "Default")
      (node (ref "P7") (pin "3") (pinfunction "3_3") (pintype "passive"))
      (node (ref "Q29") (pin "5") (pinfunction "PBRST_5") (pintype "passive"))
      (node (ref "S1") (pin "2") (pinfunction "NO_2") (pintype "passive"))
    )
    (net (code "30") (name "Net-(Q30-COMP)") (class "Default")
      (node (ref "C206") (pin "2") (pinfunction "2_2") (pintype "passive"))
      (node (ref "Q30") (pin "6") (pinfunction "COMP_6") (pintype "passive"))
    )
    (net (code "31") (name "Net-(Q30-FB)") (class "Default")
      (node (ref "Q30") (pin "5") (pinfunction "FB_5") (pintype "passive"))
      (node (ref "R104") (pin "1") (pinfunction "1_1") (pintype "passive"))
      (node (ref "R106") (pin "2") (pinfunction "2_2") (pintype "passive"))
    )
    (net (code "32") (name "Net-(Q30-SS)") (class "Default")
      (node (ref "C78") (pin "2") (pinfunction "2_2") (pintype "passive"))
      (node (ref "Q30") (pin "8") (pinfunction "SS_8") (pintype "passive"))
    )
    (net (code "33") (name "Net-(Q30-SW)") (class "Default")
      (node (ref "C205") (pin "1") (pinfunction "1_1") (pintype "passive"))
      (node (ref "L7") (pin "1") (pinfunction "1_1") (pintype "passive"))
      (node (ref "Q30") (pin "3") (pinfunction "SW_3") (pintype "passive"))
    )
    (net (code "34") (name "Net-(T2-D)") (class "Default")
      (node (ref "C200") (pin "1") (pinfunction "1_1") (pintype "passive"))
      (node (ref "L4") (pin "1") (pinfunction "1_1") (pintype "passive"))
      (node (ref "Q20") (pin "10") (pinfunction "SW_10") (pintype "passive"))
      (node (ref "Q20") (pin "8") (pinfunction "SW_8") (pintype "passive"))
      (node (ref "Q20") (pin "9") (pinfunction "SW_9") (pintype "passive"))
      (node (ref "T2") (pin "2") (pinfunction "D_2") (pintype "passive"))
    )
  )
)
